# Madre_Sensor_Hall.net
KiCad netlist of a schematic drawn in EAGLE
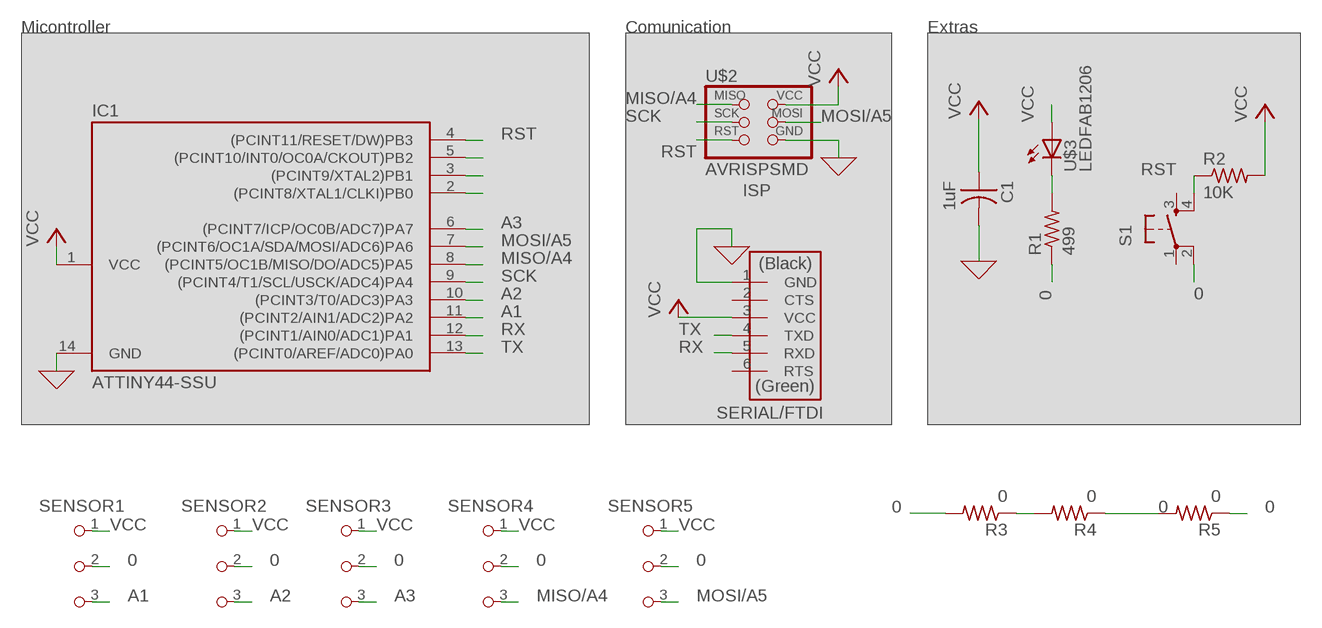
[diagram p0: schematic, sheet 1]

(export (version "E")
  (design (tool "Eeschema 10.0.6"))
  (components
    (comp (ref "C1")
      (value "1uF")
      (footprint "eagle-import:C1206FAB")
      (libsource (lib "eagle-import") (part "CAP-US1206FAB"))
    )
    (comp (ref "IC1")
      (value "ATTINY44-SSU")
      (footprint "eagle-import:SOIC14")
      (libsource (lib "eagle-import") (part "ATTINY44-SSU"))
    )
    (comp (ref "R1")
      (value "499")
      (footprint "eagle-import:R1206FAB")
      (libsource (lib "eagle-import") (part "RES-US1206FAB"))
    )
    (comp (ref "R2")
      (value "10K")
      (footprint "eagle-import:R1206FAB")
      (libsource (lib "eagle-import") (part "RES-US1206FAB"))
    )
    (comp (ref "R3")
      (value "0")
      (footprint "eagle-import:R1206FAB")
      (libsource (lib "eagle-import") (part "RES-US1206FAB"))
    )
    (comp (ref "R4")
      (value "0")
      (footprint "eagle-import:R1206FAB")
      (libsource (lib "eagle-import") (part "RES-US1206FAB"))
    )
    (comp (ref "R5")
      (value "0")
      (footprint "eagle-import:R1206FAB")
      (libsource (lib "eagle-import") (part "RES-US1206FAB"))
    )
    (comp (ref "S1")
      (value "6MM_SWITCH6MM_SWITCH")
      (footprint "eagle-import:6MM_SWITCH")
      (libsource (lib "eagle-import") (part "6MM_SWITCH6MM_SWITCH"))
    )
    (comp (ref "SENSOR1")
      (value "SPDTSWITCH")
      (footprint "eagle-import:SPDTSWITCH")
      (libsource (lib "eagle-import") (part "SPDTSWITCH"))
    )
    (comp (ref "SENSOR2")
      (value "SPDTSWITCH")
      (footprint "eagle-import:SPDTSWITCH")
      (libsource (lib "eagle-import") (part "SPDTSWITCH"))
    )
    (comp (ref "SENSOR3")
      (value "SPDTSWITCH")
      (footprint "eagle-import:SPDTSWITCH")
      (libsource (lib "eagle-import") (part "SPDTSWITCH"))
    )
    (comp (ref "SENSOR4")
      (value "SPDTSWITCH")
      (footprint "eagle-import:SPDTSWITCH")
      (libsource (lib "eagle-import") (part "SPDTSWITCH"))
    )
    (comp (ref "SENSOR5")
      (value "SPDTSWITCH")
      (footprint "eagle-import:SPDTSWITCH")
      (libsource (lib "eagle-import") (part "SPDTSWITCH"))
    )
    (comp (ref "U$1")
      (value "FTDI-SMD-HEADER")
      (footprint "eagle-import:1X06SMD")
      (libsource (lib "eagle-import") (part "FTDI-SMD-HEADER"))
    )
    (comp (ref "U$2")
      (value "AVRISPSMD")
      (footprint "eagle-import:2X03SMD")
      (libsource (lib "eagle-import") (part "AVRISPSMD"))
    )
    (comp (ref "U$3")
      (value "LEDFAB1206")
      (footprint "eagle-import:LED1206FAB")
      (libsource (lib "eagle-import") (part "LEDFAB1206"))
    )
  )
  (nets
    (net (code "1") (name "/A1") (class "Default")
      (node (ref "IC1") (pin "11") (pinfunction "(PCINT2/AIN1/ADC2)PA2_11") (pintype "bidirectional"))
      (node (ref "SENSOR1") (pin "3") (pinfunction "3_3") (pintype "passive"))
    )
    (net (code "2") (name "/A2") (class "Default")
      (node (ref "IC1") (pin "10") (pinfunction "(PCINT3/T0/ADC3)PA3_10") (pintype "bidirectional"))
      (node (ref "SENSOR2") (pin "3") (pinfunction "3_3") (pintype "passive"))
    )
    (net (code "3") (name "/A3") (class "Default")
      (node (ref "IC1") (pin "6") (pinfunction "(PCINT7/ICP/OC0B/ADC7)PA7_6") (pintype "bidirectional"))
      (node (ref "SENSOR3") (pin "3") (pinfunction "3_3") (pintype "passive"))
    )
    (net (code "4") (name "/MISO{slash}A4") (class "Default")
      (node (ref "IC1") (pin "8") (pinfunction "(PCINT5/OC1B/MISO/DO/ADC5)PA5_8") (pintype "bidirectional"))
      (node (ref "SENSOR4") (pin "3") (pinfunction "3_3") (pintype "passive"))
      (node (ref "U$2") (pin "1") (pinfunction "MISO_1") (pintype "passive"))
    )
    (net (code "5") (name "/MOSI{slash}A5") (class "Default")
      (node (ref "IC1") (pin "7") (pinfunction "(PCINT6/OC1A/SDA/MOSI/ADC6)PA6_7") (pintype "bidirectional"))
      (node (ref "SENSOR5") (pin "3") (pinfunction "3_3") (pintype "passive"))
      (node (ref "U$2") (pin "4") (pinfunction "MOSI_4") (pintype "passive"))
    )
    (net (code "6") (name "/RST") (class "Default")
      (node (ref "IC1") (pin "4") (pinfunction "(PCINT11/RESET/DW)PB3_4") (pintype "bidirectional"))
      (node (ref "R2") (pin "1") (pinfunction "1_1") (pintype "passive"))
      (node (ref "S1") (pin "4") (pinfunction "S1_4") (pintype "passive"))
      (node (ref "U$2") (pin "5") (pinfunction "RST_5") (pintype "passive"))
    )
    (net (code "7") (name "/RX") (class "Default")
      (node (ref "IC1") (pin "12") (pinfunction "(PCINT1/AIN0/ADC1)PA1_12") (pintype "bidirectional"))
      (node (ref "U$1") (pin "5") (pinfunction "RXD_5") (pintype "bidirectional"))
    )
    (net (code "8") (name "/SCK") (class "Default")
      (node (ref "IC1") (pin "9") (pinfunction "(PCINT4/T1/SCL/USCK/ADC4)PA4_9") (pintype "bidirectional"))
      (node (ref "U$2") (pin "3") (pinfunction "SCK_3") (pintype "passive"))
    )
    (net (code "9") (name "/TX") (class "Default")
      (node (ref "IC1") (pin "13") (pinfunction "(PCINT0/AREF/ADC0)PA0_13") (pintype "bidirectional"))
      (node (ref "U$1") (pin "4") (pinfunction "TXD_4") (pintype "bidirectional"))
    )
    (net (code "10") (name "GND") (class "Default")
      (node (ref "C1") (pin "2") (pinfunction "2_2") (pintype "passive"))
      (node (ref "IC1") (pin "14") (pinfunction "GND_14") (pintype "power_in"))
      (node (ref "R1") (pin "1") (pinfunction "1_1") (pintype "passive"))
      (node (ref "R3") (pin "1") (pinfunction "1_1") (pintype "passive"))
      (node (ref "R3") (pin "2") (pinfunction "2_2") (pintype "passive"))
      (node (ref "R4") (pin "1") (pinfunction "1_1") (pintype "passive"))
      (node (ref "R4") (pin "2") (pinfunction "2_2") (pintype "passive"))
      (node (ref "R5") (pin "1") (pinfunction "1_1") (pintype "passive"))
      (node (ref "R5") (pin "2") (pinfunction "2_2") (pintype "passive"))
      (node (ref "S1") (pin "2") (pinfunction "P1_2") (pintype "passive"))
      (node (ref "SENSOR1") (pin "2") (pinfunction "2_2") (pintype "passive"))
      (node (ref "SENSOR2") (pin "2") (pinfunction "2_2") (pintype "passive"))
      (node (ref "SENSOR3") (pin "2") (pinfunction "2_2") (pintype "passive"))
      (node (ref "SENSOR4") (pin "2") (pinfunction "2_2") (pintype "passive"))
      (node (ref "SENSOR5") (pin "2") (pinfunction "2_2") (pintype "passive"))
      (node (ref "U$1") (pin "1") (pinfunction "GND_1") (pintype "bidirectional"))
      (node (ref "U$2") (pin "6") (pinfunction "GND_6") (pintype "passive"))
    )
    (net (code "11") (name "Net-(U$3-C)") (class "Default")
      (node (ref "R1") (pin "2") (pinfunction "2_2") (pintype "passive"))
      (node (ref "U$3") (pin "2") (pinfunction "C_2") (pintype "passive"))
    )
    (net (code "12") (name "VCC") (class "Default")
      (node (ref "C1") (pin "1") (pinfunction "1_1") (pintype "passive"))
      (node (ref "IC1") (pin "1") (pinfunction "VCC_1") (pintype "power_in"))
      (node (ref "R2") (pin "2") (pinfunction "2_2") (pintype "passive"))
      (node (ref "SENSOR1") (pin "1") (pinfunction "1_1") (pintype "passive"))
      (node (ref "SENSOR2") (pin "1") (pinfunction "1_1") (pintype "passive"))
      (node (ref "SENSOR3") (pin "1") (pinfunction "1_1") (pintype "passive"))
      (node (ref "SENSOR4") (pin "1") (pinfunction "1_1") (pintype "passive"))
      (node (ref "SENSOR5") (pin "1") (pinfunction "1_1") (pintype "passive"))
      (node (ref "U$1") (pin "3") (pinfunction "VCC_3") (pintype "bidirectional"))
      (node (ref "U$2") (pin "2") (pinfunction "VCC_2") (pintype "passive"))
      (node (ref "U$3") (pin "1") (pinfunction "A_1") (pintype "passive"))
    )
    (net (code "13") (name "unconnected-(IC1-(PCINT8{slash}XTAL1{slash}CLKI)PB0-Pad2)") (class "Default")
      (node (ref "IC1") (pin "2") (pinfunction "(PCINT8/XTAL1/CLKI)PB0_2") (pintype "bidirectional"))
    )
    (net (code "14") (name "unconnected-(IC1-(PCINT9{slash}XTAL2)PB1-Pad3)") (class "Default")
      (node (ref "IC1") (pin "3") (pinfunction "(PCINT9/XTAL2)PB1_3") (pintype "bidirectional"))
    )
    (net (code "15") (name "unconnected-(IC1-(PCINT10{slash}INT0{slash}OC0A{slash}CKOUT)PB2-Pad5)") (class "Default")
      (node (ref "IC1") (pin "5") (pinfunction "(PCINT10/INT0/OC0A/CKOUT)PB2_5") (pintype "bidirectional"))
    )
    (net (code "16") (name "unconnected-(S1-P-Pad1)") (class "Default")
      (node (ref "S1") (pin "1") (pinfunction "P_1") (pintype "passive"))
    )
    (net (code "17") (name "unconnected-(S1-S-Pad3)") (class "Default")
      (node (ref "S1") (pin "3") (pinfunction "S_3") (pintype "passive"))
    )
    (net (code "18") (name "unconnected-(U$1-CTS-Pad2)") (class "Default")
      (node (ref "U$1") (pin "2") (pinfunction "CTS_2") (pintype "bidirectional"))
    )
    (net (code "19") (name "unconnected-(U$1-RTS-Pad6)") (class "Default")
      (node (ref "U$1") (pin "6") (pinfunction "RTS_6") (pintype "bidirectional"))
    )
  )
)
